# C4H_LightGate_Eyes.net
KiCad netlist of a schematic drawn in EAGLE
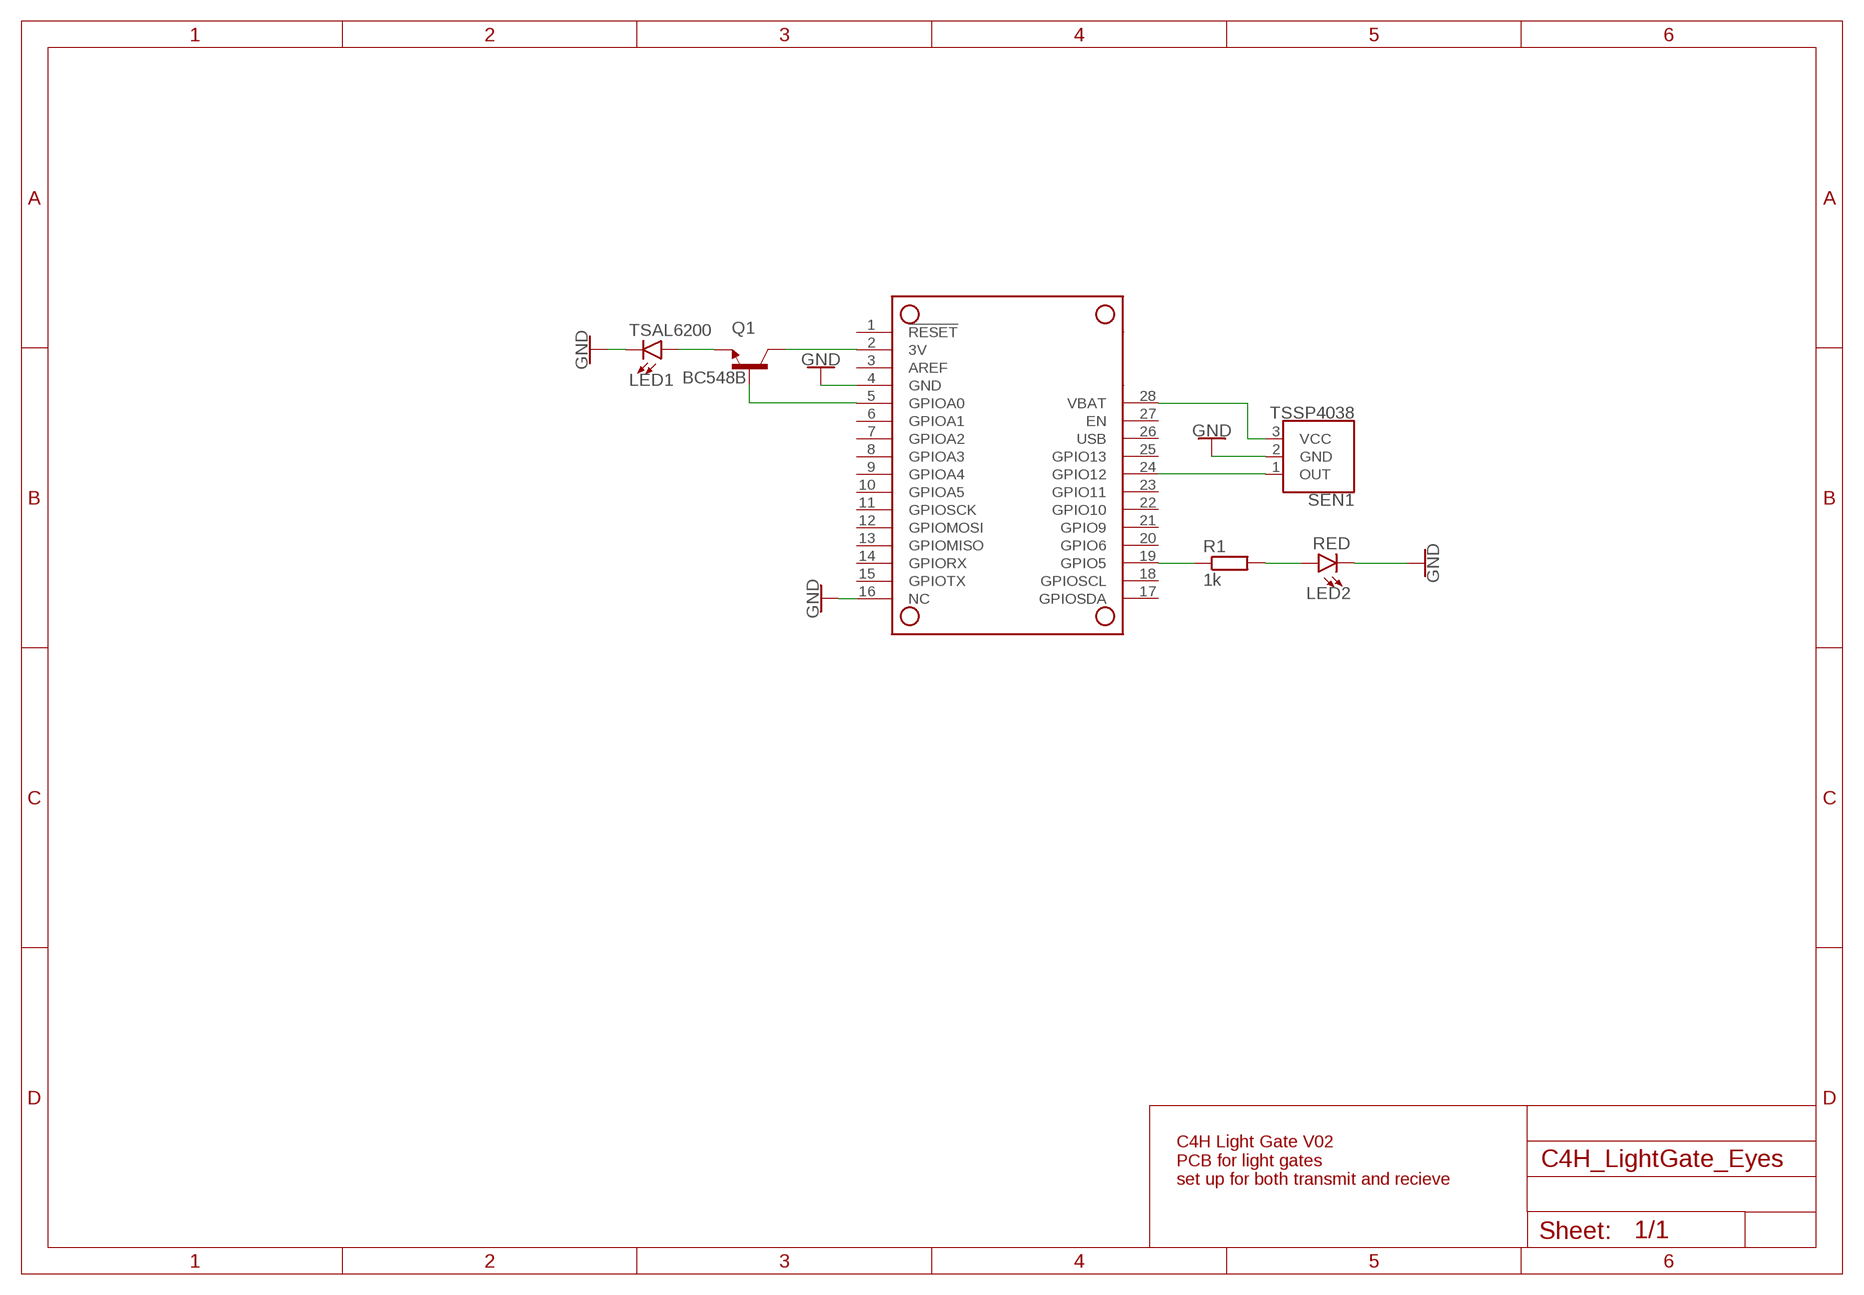
[diagram p0: schematic, sheet 1]

(export (version "E")
  (design (tool "Eeschema 10.0.6"))
  (components
    (comp (ref "LED1")
      (value "TSAL6200")
      (footprint "eagle-import:LED5MM")
      (libsource (lib "eagle-import") (part "IR-LEDIR_LED_5MM"))
    )
    (comp (ref "LED2")
      (value "RED")
      (footprint "eagle-import:LED5MM")
      (libsource (lib "eagle-import") (part "LED-5MMIR_LED_5MM"))
    )
    (comp (ref "MS1")
      (value "FEATHERWING")
      (footprint "eagle-import:FEATHERWING")
      (libsource (lib "eagle-import") (part "FEATHERWING"))
    )
    (comp (ref "Q1")
      (value "BC548B")
      (footprint "eagle-import:TO92-EBC")
      (libsource (lib "eagle-import") (part "BC548B"))
    )
    (comp (ref "R1")
      (value "1k")
      (footprint "eagle-import:0207_7")
      (libsource (lib "eagle-import") (part "1/4W_0207"))
    )
    (comp (ref "SEN1")
      (value "TSSP4038")
      (footprint "eagle-import:TSSP40")
      (libsource (lib "eagle-import") (part "TSSP40RA"))
    )
  )
  (nets
    (net (code "1") (name "/USB") (class "Default")
      (node (ref "MS1") (pin "26") (pinfunction "USB_26") (pintype "power_in"))
    )
    (net (code "2") (name "GND") (class "Default")
      (node (ref "LED1") (pin "K") (pinfunction "C_K") (pintype "passive"))
      (node (ref "LED2") (pin "K") (pinfunction "C_K") (pintype "passive"))
      (node (ref "MS1") (pin "16") (pinfunction "NC_16") (pintype "passive"))
      (node (ref "MS1") (pin "4") (pinfunction "GND_4") (pintype "power_in"))
      (node (ref "SEN1") (pin "2") (pinfunction "GND_2") (pintype "bidirectional"))
    )
    (net (code "3") (name "Net-(LED1-PadA)") (class "Default")
      (node (ref "LED1") (pin "A") (pinfunction "A_A") (pintype "passive"))
      (node (ref "Q1") (pin "E") (pinfunction "E_E") (pintype "passive"))
    )
    (net (code "4") (name "Net-(LED2-PadA)") (class "Default")
      (node (ref "LED2") (pin "A") (pinfunction "A_A") (pintype "passive"))
      (node (ref "R1") (pin "2") (pinfunction "2_2") (pintype "passive"))
    )
    (net (code "5") (name "Net-(MS1-3V)") (class "Default")
      (node (ref "MS1") (pin "2") (pinfunction "3V_2") (pintype "power_in"))
      (node (ref "Q1") (pin "C") (pinfunction "C_C") (pintype "passive"))
    )
    (net (code "6") (name "Net-(MS1-GPIO5)") (class "Default")
      (node (ref "MS1") (pin "19") (pinfunction "GPIO5_19") (pintype "bidirectional"))
      (node (ref "R1") (pin "1") (pinfunction "1_1") (pintype "passive"))
    )
    (net (code "7") (name "Net-(MS1-GPIO12)") (class "Default")
      (node (ref "MS1") (pin "24") (pinfunction "GPIO12_24") (pintype "bidirectional"))
      (node (ref "SEN1") (pin "1") (pinfunction "OUT_1") (pintype "bidirectional"))
    )
    (net (code "8") (name "Net-(MS1-GPIOA0)") (class "Default")
      (node (ref "MS1") (pin "5") (pinfunction "GPIOA0_5") (pintype "bidirectional"))
      (node (ref "Q1") (pin "B") (pinfunction "B_B") (pintype "passive"))
    )
    (net (code "9") (name "Net-(MS1-VBAT)") (class "Default")
      (node (ref "MS1") (pin "28") (pinfunction "VBAT_28") (pintype "power_in"))
      (node (ref "SEN1") (pin "3") (pinfunction "VCC_3") (pintype "bidirectional"))
    )
    (net (code "10") (name "unconnected-(MS1-AREF-Pad3)") (class "Default")
      (node (ref "MS1") (pin "3") (pinfunction "AREF_3") (pintype "passive"))
    )
    (net (code "11") (name "unconnected-(MS1-EN-Pad27)") (class "Default")
      (node (ref "MS1") (pin "27") (pinfunction "EN_27") (pintype "passive"))
    )
    (net (code "12") (name "unconnected-(MS1-GPIO6-Pad20)") (class "Default")
      (node (ref "MS1") (pin "20") (pinfunction "GPIO6_20") (pintype "bidirectional"))
    )
    (net (code "13") (name "unconnected-(MS1-GPIO9-Pad21)") (class "Default")
      (node (ref "MS1") (pin "21") (pinfunction "GPIO9_21") (pintype "bidirectional"))
    )
    (net (code "14") (name "unconnected-(MS1-GPIO10-Pad22)") (class "Default")
      (node (ref "MS1") (pin "22") (pinfunction "GPIO10_22") (pintype "bidirectional"))
    )
    (net (code "15") (name "unconnected-(MS1-GPIO11-Pad23)") (class "Default")
      (node (ref "MS1") (pin "23") (pinfunction "GPIO11_23") (pintype "bidirectional"))
    )
    (net (code "16") (name "unconnected-(MS1-GPIO13-Pad25)") (class "Default")
      (node (ref "MS1") (pin "25") (pinfunction "GPIO13_25") (pintype "bidirectional"))
    )
    (net (code "17") (name "unconnected-(MS1-GPIOA1-Pad6)") (class "Default")
      (node (ref "MS1") (pin "6") (pinfunction "GPIOA1_6") (pintype "bidirectional"))
    )
    (net (code "18") (name "unconnected-(MS1-GPIOA2-Pad7)") (class "Default")
      (node (ref "MS1") (pin "7") (pinfunction "GPIOA2_7") (pintype "bidirectional"))
    )
    (net (code "19") (name "unconnected-(MS1-GPIOA3-Pad8)") (class "Default")
      (node (ref "MS1") (pin "8") (pinfunction "GPIOA3_8") (pintype "bidirectional"))
    )
    (net (code "20") (name "unconnected-(MS1-GPIOA4-Pad9)") (class "Default")
      (node (ref "MS1") (pin "9") (pinfunction "GPIOA4_9") (pintype "bidirectional"))
    )
    (net (code "21") (name "unconnected-(MS1-GPIOA5-Pad10)") (class "Default")
      (node (ref "MS1") (pin "10") (pinfunction "GPIOA5_10") (pintype "bidirectional"))
    )
    (net (code "22") (name "unconnected-(MS1-GPIOMISO-Pad13)") (class "Default")
      (node (ref "MS1") (pin "13") (pinfunction "GPIOMISO_13") (pintype "bidirectional"))
    )
    (net (code "23") (name "unconnected-(MS1-GPIOMOSI-Pad12)") (class "Default")
      (node (ref "MS1") (pin "12") (pinfunction "GPIOMOSI_12") (pintype "bidirectional"))
    )
    (net (code "24") (name "unconnected-(MS1-GPIORX-Pad14)") (class "Default")
      (node (ref "MS1") (pin "14") (pinfunction "GPIORX_14") (pintype "bidirectional"))
    )
    (net (code "25") (name "unconnected-(MS1-GPIOSCK-Pad11)") (class "Default")
      (node (ref "MS1") (pin "11") (pinfunction "GPIOSCK_11") (pintype "bidirectional"))
    )
    (net (code "26") (name "unconnected-(MS1-GPIOSCL-Pad18)") (class "Default")
      (node (ref "MS1") (pin "18") (pinfunction "GPIOSCL_18") (pintype "bidirectional"))
    )
    (net (code "27") (name "unconnected-(MS1-GPIOSDA-Pad17)") (class "Default")
      (node (ref "MS1") (pin "17") (pinfunction "GPIOSDA_17") (pintype "bidirectional"))
    )
    (net (code "28") (name "unconnected-(MS1-GPIOTX-Pad15)") (class "Default")
      (node (ref "MS1") (pin "15") (pinfunction "GPIOTX_15") (pintype "bidirectional"))
    )
    (net (code "29") (name "unconnected-(MS1-~{RESET}-Pad1)") (class "Default")
      (node (ref "MS1") (pin "1") (pinfunction "~{RESET}_1") (pintype "input"))
    )
  )
)
